# pc_max30001_brk_v1_0.net
KiCad netlist of a schematic drawn in EAGLE
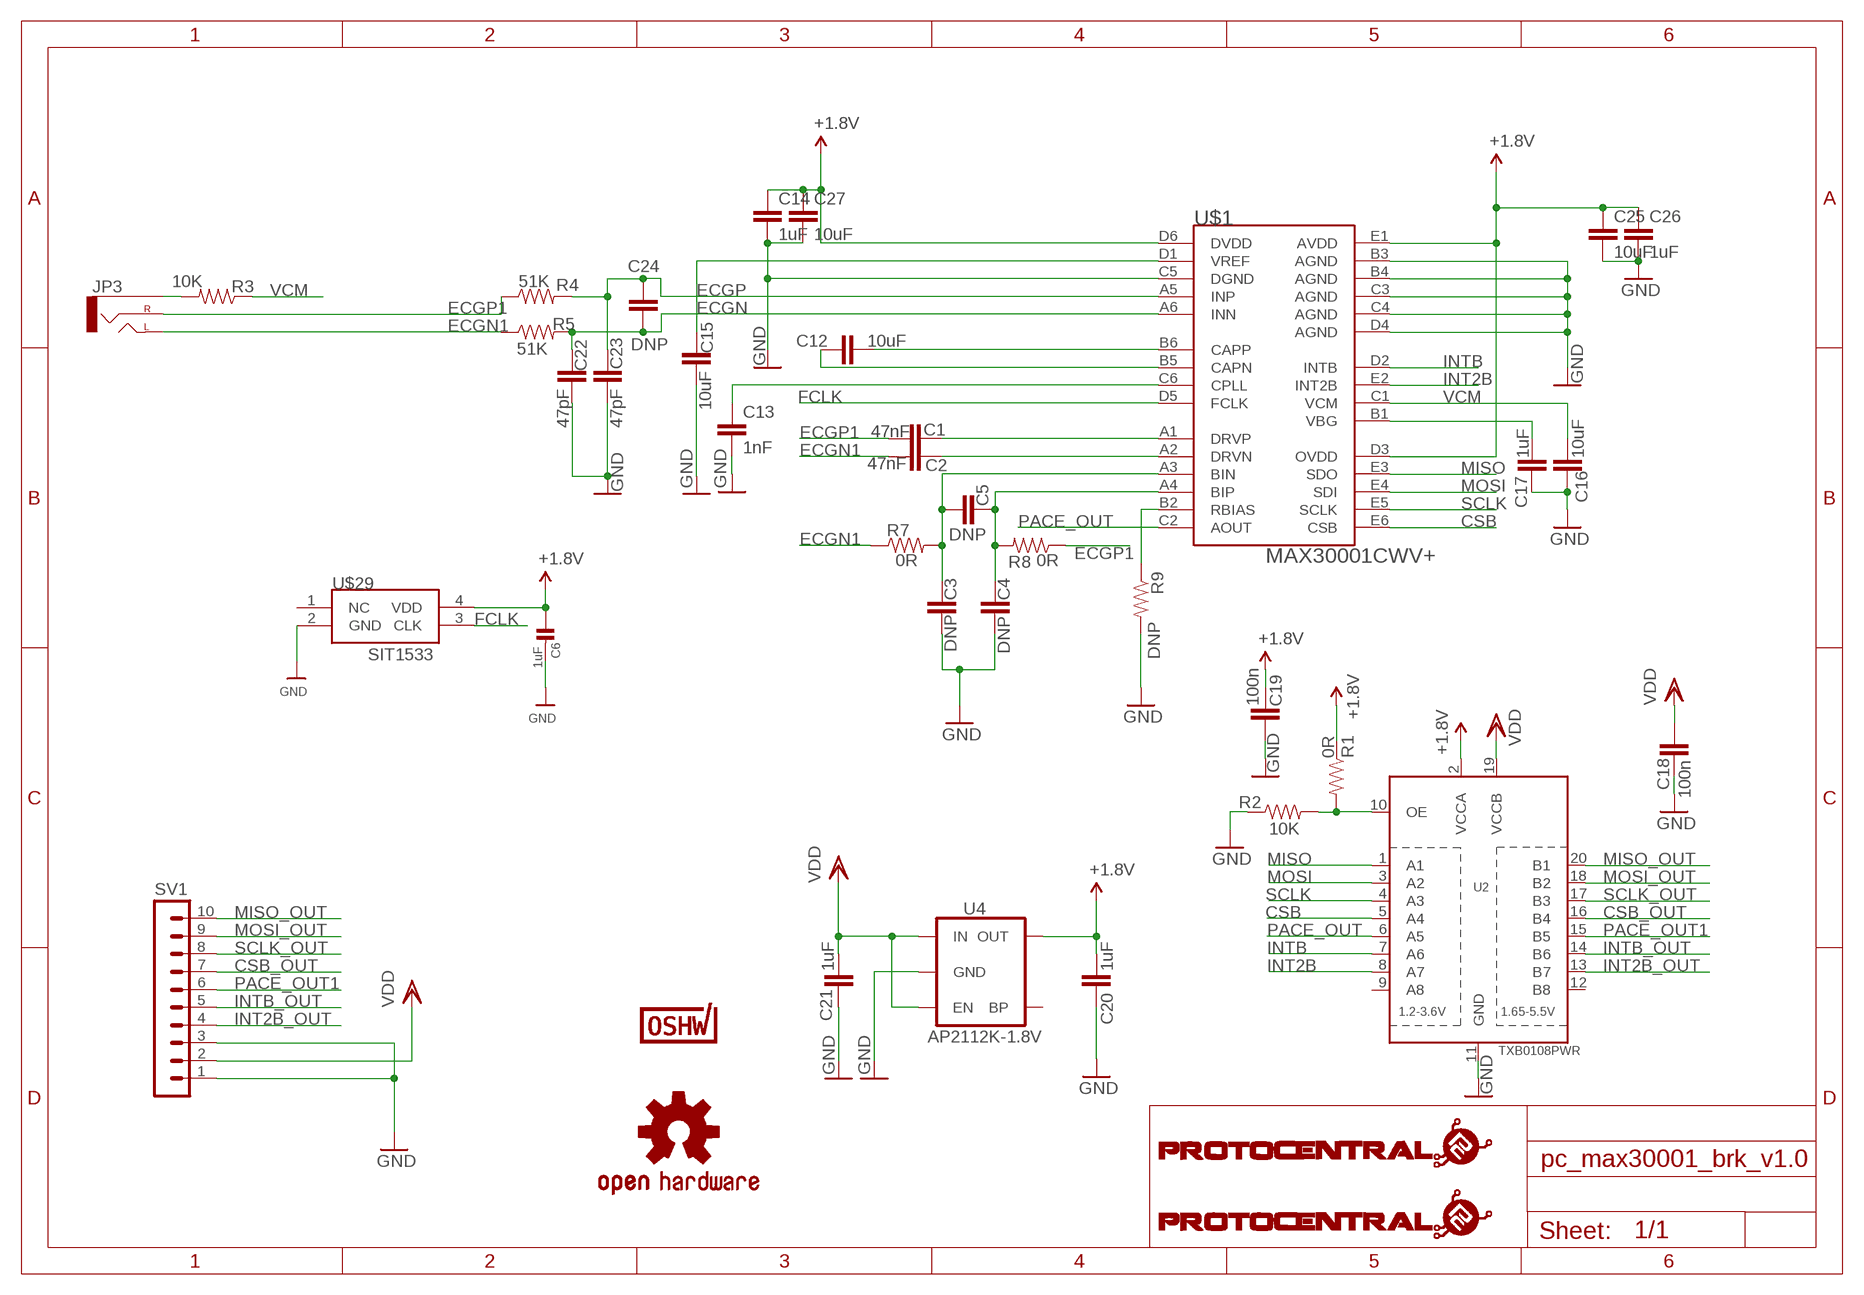
[diagram p0: schematic, sheet 1]

(export (version "E")
  (design (tool "Eeschema 10.0.6"))
  (components
    (comp (ref "C1")
      (value "47nF")
      (footprint "eagle-import:C0402")
      (libsource (lib "eagle-import") (part "C-EUC0402"))
    )
    (comp (ref "C2")
      (value "47nF")
      (footprint "eagle-import:C0402")
      (libsource (lib "eagle-import") (part "C-EUC0402"))
    )
    (comp (ref "C3")
      (value "DNP")
      (footprint "eagle-import:C0402")
      (libsource (lib "eagle-import") (part "C-EUC0402"))
    )
    (comp (ref "C4")
      (value "DNP")
      (footprint "eagle-import:C0402")
      (libsource (lib "eagle-import") (part "C-EUC0402"))
    )
    (comp (ref "C5")
      (value "DNP")
      (footprint "eagle-import:C0402")
      (libsource (lib "eagle-import") (part "C-EUC0402"))
    )
    (comp (ref "C6")
      (value "1uF")
      (footprint "eagle-import:0402")
      (libsource (lib "eagle-import") (part "CAP_CERAMIC0402"))
    )
    (comp (ref "C12")
      (value "10uF")
      (footprint "eagle-import:C0805")
      (libsource (lib "eagle-import") (part "C-EUC0805"))
    )
    (comp (ref "C13")
      (value "1nF")
      (footprint "eagle-import:C0402")
      (libsource (lib "eagle-import") (part "C-EUC0402"))
    )
    (comp (ref "C14")
      (value "1uF")
      (footprint "eagle-import:C0402")
      (libsource (lib "eagle-import") (part "C-EUC0402"))
    )
    (comp (ref "C15")
      (value "10uF")
      (footprint "eagle-import:C0805")
      (libsource (lib "eagle-import") (part "C-EUC0805"))
    )
    (comp (ref "C16")
      (value "10uF")
      (footprint "eagle-import:C0805")
      (libsource (lib "eagle-import") (part "C-EUC0805"))
    )
    (comp (ref "C17")
      (value "1uF")
      (footprint "eagle-import:C0402")
      (libsource (lib "eagle-import") (part "C-EUC0402"))
    )
    (comp (ref "C18")
      (value "100n")
      (footprint "eagle-import:C0402")
      (libsource (lib "eagle-import") (part "C-EUC0402"))
    )
    (comp (ref "C19")
      (value "100n")
      (footprint "eagle-import:C0402")
      (libsource (lib "eagle-import") (part "C-EUC0402"))
    )
    (comp (ref "C20")
      (value "1uF")
      (footprint "eagle-import:C0805")
      (libsource (lib "eagle-import") (part "C-EUC0805"))
    )
    (comp (ref "C21")
      (value "1uF")
      (footprint "eagle-import:C0805")
      (libsource (lib "eagle-import") (part "C-EUC0805"))
    )
    (comp (ref "C22")
      (value "47pF")
      (footprint "eagle-import:C0402")
      (libsource (lib "eagle-import") (part "C-EUC0402"))
    )
    (comp (ref "C23")
      (value "47pF")
      (footprint "eagle-import:C0402")
      (libsource (lib "eagle-import") (part "C-EUC0402"))
    )
    (comp (ref "C24")
      (value "DNP")
      (footprint "eagle-import:C0402")
      (libsource (lib "eagle-import") (part "C-EUC0402"))
    )
    (comp (ref "C25")
      (value "10uF")
      (footprint "eagle-import:C0805")
      (libsource (lib "eagle-import") (part "C-EUC0805"))
    )
    (comp (ref "C26")
      (value "1uF")
      (footprint "eagle-import:C0402")
      (libsource (lib "eagle-import") (part "C-EUC0402"))
    )
    (comp (ref "C27")
      (value "10uF")
      (footprint "eagle-import:C0805")
      (libsource (lib "eagle-import") (part "C-EUC0805"))
    )
    (comp (ref "JP3")
      (value "AUDIO-JACKSMD2")
      (footprint "eagle-import:AUDIO-JACK-3.5MM-SMD")
      (libsource (lib "eagle-import") (part "AUDIO-JACKSMD2"))
    )
    (comp (ref "R1")
      (value "0R")
      (footprint "eagle-import:0805")
      (libsource (lib "eagle-import") (part "RESISTOR0805-RES"))
    )
    (comp (ref "R2")
      (value "10K")
      (footprint "eagle-import:0805")
      (libsource (lib "eagle-import") (part "RESISTOR0805-RES"))
    )
    (comp (ref "R3")
      (value "10K")
      (footprint "eagle-import:0805")
      (libsource (lib "eagle-import") (part "RESISTOR0805-RES"))
    )
    (comp (ref "R4")
      (value "51K")
      (footprint "eagle-import:0805")
      (libsource (lib "eagle-import") (part "RESISTOR0805-RES"))
    )
    (comp (ref "R5")
      (value "51K")
      (footprint "eagle-import:0805")
      (libsource (lib "eagle-import") (part "RESISTOR0805-RES"))
    )
    (comp (ref "R7")
      (value "0R")
      (footprint "eagle-import:0402-RES")
      (libsource (lib "eagle-import") (part "RESISTOR0402-RES"))
    )
    (comp (ref "R8")
      (value "0R")
      (footprint "eagle-import:0402-RES")
      (libsource (lib "eagle-import") (part "RESISTOR0402-RES"))
    )
    (comp (ref "R9")
      (value "DNP")
      (footprint "eagle-import:0402-RES")
      (libsource (lib "eagle-import") (part "RESISTOR0402-RES"))
    )
    (comp (ref "SV1")
      (value "MA10-1")
      (footprint "eagle-import:MA10-1")
      (libsource (lib "eagle-import") (part "MA10-1"))
    )
    (comp (ref "U$1")
      (value "MAX30001CWV+")
      (footprint "eagle-import:30WLP")
      (libsource (lib "eagle-import") (part "MAX30001CWV+"))
    )
    (comp (ref "U$3")
      (value "PROTY-LOGO")
      (footprint "eagle-import:LOGO-PROTY")
      (libsource (lib "eagle-import") (part "PROTY-LOGO"))
    )
    (comp (ref "U$4")
      (value "PROTY_LOGO_WITH_TEXT")
      (footprint "eagle-import:PROTY_WITH_TEXT")
      (libsource (lib "eagle-import") (part "PROTY_LOGO_WITH_TEXT"))
    )
    (comp (ref "U$6")
      (value "OSHW-LOGOS")
      (footprint "eagle-import:OSHW-LOGO-S")
      (libsource (lib "eagle-import") (part "OSHW-LOGOS"))
    )
    (comp (ref "U$7")
      (value "CERT-SMALL")
      (footprint "eagle-import:CERT-SMALL-SILK")
      (libsource (lib "eagle-import") (part "CERT-SMALL"))
    )
    (comp (ref "U$29")
      (value "SIT1533")
      (footprint "eagle-import:SIT1533")
      (libsource (lib "eagle-import") (part "SIT1533"))
    )
    (comp (ref "U2")
      (value "TXB0108PWR")
      (footprint "eagle-import:TSSOP20")
      (libsource (lib "eagle-import") (part "TXB0108PWR"))
    )
    (comp (ref "U4")
      (value "AP2112K-1.8V")
      (footprint "eagle-import:SOT23-5")
      (libsource (lib "eagle-import") (part "V_REG_LDOSMD"))
    )
  )
  (nets
    (net (code "1") (name "+1.8V") (class "Default")
      (node (ref "C14") (pin "1") (pinfunction "1_1") (pintype "passive"))
      (node (ref "C19") (pin "2") (pinfunction "2_2") (pintype "passive"))
      (node (ref "C20") (pin "2") (pinfunction "2_2") (pintype "passive"))
      (node (ref "C25") (pin "1") (pinfunction "1_1") (pintype "passive"))
      (node (ref "C26") (pin "1") (pinfunction "1_1") (pintype "passive"))
      (node (ref "C27") (pin "1") (pinfunction "1_1") (pintype "passive"))
      (node (ref "C6") (pin "1") (pinfunction "P$1_1") (pintype "passive"))
      (node (ref "R1") (pin "1") (pinfunction "1_1") (pintype "passive"))
      (node (ref "U$1") (pin "D3") (pinfunction "OVDD_D3") (pintype "bidirectional"))
      (node (ref "U$1") (pin "D6") (pinfunction "DVDD_D6") (pintype "bidirectional"))
      (node (ref "U$1") (pin "E1") (pinfunction "AVDD_E1") (pintype "bidirectional"))
      (node (ref "U$29") (pin "4") (pinfunction "VDD_4") (pintype "bidirectional"))
      (node (ref "U2") (pin "2") (pinfunction "VCCA_2") (pintype "bidirectional"))
      (node (ref "U4") (pin "5") (pinfunction "OUT_5") (pintype "passive"))
    )
    (net (code "2") (name "/CSB") (class "Default")
      (node (ref "U$1") (pin "E6") (pinfunction "CSB_E6") (pintype "bidirectional"))
      (node (ref "U2") (pin "5") (pinfunction "A4_5") (pintype "bidirectional"))
    )
    (net (code "3") (name "/CSB_OUT") (class "Default")
      (node (ref "SV1") (pin "7") (pinfunction "7_7") (pintype "passive"))
      (node (ref "U2") (pin "16") (pinfunction "B4_16") (pintype "bidirectional"))
    )
    (net (code "4") (name "/ECGN") (class "Default")
      (node (ref "C22") (pin "1") (pinfunction "1_1") (pintype "passive"))
      (node (ref "C24") (pin "2") (pinfunction "2_2") (pintype "passive"))
      (node (ref "R5") (pin "2") (pinfunction "2_2") (pintype "passive"))
      (node (ref "U$1") (pin "A6") (pinfunction "INN_A6") (pintype "bidirectional"))
    )
    (net (code "5") (name "/ECGN1") (class "Default")
      (node (ref "C2") (pin "1") (pinfunction "1_1") (pintype "passive"))
      (node (ref "JP3") (pin "TIP") (pinfunction "LEFT_TIP") (pintype "bidirectional"))
      (node (ref "R5") (pin "1") (pinfunction "1_1") (pintype "passive"))
      (node (ref "R7") (pin "1") (pinfunction "1_1") (pintype "passive"))
    )
    (net (code "6") (name "/ECGP") (class "Default")
      (node (ref "C23") (pin "1") (pinfunction "1_1") (pintype "passive"))
      (node (ref "C24") (pin "1") (pinfunction "1_1") (pintype "passive"))
      (node (ref "R4") (pin "2") (pinfunction "2_2") (pintype "passive"))
      (node (ref "U$1") (pin "A5") (pinfunction "INP_A5") (pintype "bidirectional"))
    )
    (net (code "7") (name "/ECGP1") (class "Default")
      (node (ref "C1") (pin "1") (pinfunction "1_1") (pintype "passive"))
      (node (ref "JP3") (pin "RING") (pinfunction "RIGHT_RING") (pintype "bidirectional"))
      (node (ref "R4") (pin "1") (pinfunction "1_1") (pintype "passive"))
      (node (ref "R8") (pin "1") (pinfunction "1_1") (pintype "passive"))
    )
    (net (code "8") (name "/FCLK") (class "Default")
      (node (ref "U$1") (pin "D5") (pinfunction "FCLK_D5") (pintype "bidirectional"))
      (node (ref "U$29") (pin "3") (pinfunction "CLK_3") (pintype "bidirectional"))
    )
    (net (code "9") (name "/INT2B") (class "Default")
      (node (ref "U$1") (pin "E2") (pinfunction "INT2B_E2") (pintype "bidirectional"))
      (node (ref "U2") (pin "8") (pinfunction "A7_8") (pintype "bidirectional"))
    )
    (net (code "10") (name "/INT2B_OUT") (class "Default")
      (node (ref "SV1") (pin "4") (pinfunction "4_4") (pintype "passive"))
      (node (ref "U2") (pin "13") (pinfunction "B7_13") (pintype "bidirectional"))
    )
    (net (code "11") (name "/INTB") (class "Default")
      (node (ref "U$1") (pin "D2") (pinfunction "INTB_D2") (pintype "bidirectional"))
      (node (ref "U2") (pin "7") (pinfunction "A6_7") (pintype "bidirectional"))
    )
    (net (code "12") (name "/INTB_OUT") (class "Default")
      (node (ref "SV1") (pin "5") (pinfunction "5_5") (pintype "passive"))
      (node (ref "U2") (pin "14") (pinfunction "B6_14") (pintype "bidirectional"))
    )
    (net (code "13") (name "/MISO") (class "Default")
      (node (ref "U$1") (pin "E3") (pinfunction "SDO_E3") (pintype "bidirectional"))
      (node (ref "U2") (pin "1") (pinfunction "A1_1") (pintype "bidirectional"))
    )
    (net (code "14") (name "/MISO_OUT") (class "Default")
      (node (ref "SV1") (pin "10") (pinfunction "10_10") (pintype "passive"))
      (node (ref "U2") (pin "20") (pinfunction "B1_20") (pintype "bidirectional"))
    )
    (net (code "15") (name "/MOSI") (class "Default")
      (node (ref "U$1") (pin "E4") (pinfunction "SDI_E4") (pintype "bidirectional"))
      (node (ref "U2") (pin "3") (pinfunction "A2_3") (pintype "bidirectional"))
    )
    (net (code "16") (name "/MOSI_OUT") (class "Default")
      (node (ref "SV1") (pin "9") (pinfunction "9_9") (pintype "passive"))
      (node (ref "U2") (pin "18") (pinfunction "B2_18") (pintype "bidirectional"))
    )
    (net (code "17") (name "/PACE_OUT") (class "Default")
      (node (ref "U$1") (pin "C2") (pinfunction "AOUT_C2") (pintype "bidirectional"))
      (node (ref "U2") (pin "6") (pinfunction "A5_6") (pintype "bidirectional"))
    )
    (net (code "18") (name "/PACE_OUT1") (class "Default")
      (node (ref "SV1") (pin "6") (pinfunction "6_6") (pintype "passive"))
      (node (ref "U2") (pin "15") (pinfunction "B5_15") (pintype "bidirectional"))
    )
    (net (code "19") (name "/SCLK") (class "Default")
      (node (ref "U$1") (pin "E5") (pinfunction "SCLK_E5") (pintype "bidirectional"))
      (node (ref "U2") (pin "4") (pinfunction "A3_4") (pintype "bidirectional"))
    )
    (net (code "20") (name "/SCLK_OUT") (class "Default")
      (node (ref "SV1") (pin "8") (pinfunction "8_8") (pintype "passive"))
      (node (ref "U2") (pin "17") (pinfunction "B3_17") (pintype "bidirectional"))
    )
    (net (code "21") (name "/VCM") (class "Default")
      (node (ref "C16") (pin "1") (pinfunction "1_1") (pintype "passive"))
      (node (ref "R3") (pin "1") (pinfunction "1_1") (pintype "passive"))
      (node (ref "U$1") (pin "C1") (pinfunction "VCM_C1") (pintype "bidirectional"))
    )
    (net (code "22") (name "GND") (class "Default")
      (node (ref "C13") (pin "2") (pinfunction "2_2") (pintype "passive"))
      (node (ref "C14") (pin "2") (pinfunction "2_2") (pintype "passive"))
      (node (ref "C15") (pin "2") (pinfunction "2_2") (pintype "passive"))
      (node (ref "C16") (pin "2") (pinfunction "2_2") (pintype "passive"))
      (node (ref "C17") (pin "2") (pinfunction "2_2") (pintype "passive"))
      (node (ref "C18") (pin "1") (pinfunction "1_1") (pintype "passive"))
      (node (ref "C19") (pin "1") (pinfunction "1_1") (pintype "passive"))
      (node (ref "C20") (pin "1") (pinfunction "1_1") (pintype "passive"))
      (node (ref "C21") (pin "1") (pinfunction "1_1") (pintype "passive"))
      (node (ref "C22") (pin "2") (pinfunction "2_2") (pintype "passive"))
      (node (ref "C23") (pin "2") (pinfunction "2_2") (pintype "passive"))
      (node (ref "C25") (pin "2") (pinfunction "2_2") (pintype "passive"))
      (node (ref "C26") (pin "2") (pinfunction "2_2") (pintype "passive"))
      (node (ref "C27") (pin "2") (pinfunction "2_2") (pintype "passive"))
      (node (ref "C3") (pin "2") (pinfunction "2_2") (pintype "passive"))
      (node (ref "C4") (pin "2") (pinfunction "2_2") (pintype "passive"))
      (node (ref "C6") (pin "2") (pinfunction "P$2_2") (pintype "passive"))
      (node (ref "R2") (pin "1") (pinfunction "1_1") (pintype "passive"))
      (node (ref "R9") (pin "2") (pinfunction "2_2") (pintype "passive"))
      (node (ref "SV1") (pin "1") (pinfunction "1_1") (pintype "passive"))
      (node (ref "SV1") (pin "3") (pinfunction "3_3") (pintype "passive"))
      (node (ref "U$1") (pin "B3") (pinfunction "AGND_B3") (pintype "bidirectional"))
      (node (ref "U$1") (pin "B4") (pinfunction "AGND_B4") (pintype "bidirectional"))
      (node (ref "U$1") (pin "C3") (pinfunction "AGND_C3") (pintype "bidirectional"))
      (node (ref "U$1") (pin "C4") (pinfunction "AGND_C4") (pintype "bidirectional"))
      (node (ref "U$1") (pin "C5") (pinfunction "DGND_C5") (pintype "bidirectional"))
      (node (ref "U$1") (pin "D4") (pinfunction "AGND_D4") (pintype "bidirectional"))
      (node (ref "U$29") (pin "2") (pinfunction "GND_2") (pintype "bidirectional"))
      (node (ref "U2") (pin "11") (pinfunction "GND_11") (pintype "bidirectional"))
      (node (ref "U4") (pin "2") (pinfunction "GND_2") (pintype "input"))
    )
    (net (code "23") (name "Net-(JP3-PadSLEEVE)") (class "Default")
      (node (ref "JP3") (pin "SLEEVE") (pinfunction "SLEEVE_SLEEVE") (pintype "bidirectional"))
      (node (ref "R3") (pin "2") (pinfunction "2_2") (pintype "passive"))
    )
    (net (code "24") (name "Net-(U$1-BIN)") (class "Default")
      (node (ref "C3") (pin "1") (pinfunction "1_1") (pintype "passive"))
      (node (ref "C5") (pin "1") (pinfunction "1_1") (pintype "passive"))
      (node (ref "R7") (pin "2") (pinfunction "2_2") (pintype "passive"))
      (node (ref "U$1") (pin "A3") (pinfunction "BIN_A3") (pintype "bidirectional"))
    )
    (net (code "25") (name "Net-(U$1-BIP)") (class "Default")
      (node (ref "C4") (pin "1") (pinfunction "1_1") (pintype "passive"))
      (node (ref "C5") (pin "2") (pinfunction "2_2") (pintype "passive"))
      (node (ref "R8") (pin "2") (pinfunction "2_2") (pintype "passive"))
      (node (ref "U$1") (pin "A4") (pinfunction "BIP_A4") (pintype "bidirectional"))
    )
    (net (code "26") (name "Net-(U$1-CAPN)") (class "Default")
      (node (ref "C12") (pin "2") (pinfunction "2_2") (pintype "passive"))
      (node (ref "U$1") (pin "B5") (pinfunction "CAPN_B5") (pintype "bidirectional"))
    )
    (net (code "27") (name "Net-(U$1-CAPP)") (class "Default")
      (node (ref "C12") (pin "1") (pinfunction "1_1") (pintype "passive"))
      (node (ref "U$1") (pin "B6") (pinfunction "CAPP_B6") (pintype "bidirectional"))
    )
    (net (code "28") (name "Net-(U$1-CPLL)") (class "Default")
      (node (ref "C13") (pin "1") (pinfunction "1_1") (pintype "passive"))
      (node (ref "U$1") (pin "C6") (pinfunction "CPLL_C6") (pintype "bidirectional"))
    )
    (net (code "29") (name "Net-(U$1-DRVN)") (class "Default")
      (node (ref "C2") (pin "2") (pinfunction "2_2") (pintype "passive"))
      (node (ref "U$1") (pin "A2") (pinfunction "DRVN_A2") (pintype "bidirectional"))
    )
    (net (code "30") (name "Net-(U$1-DRVP)") (class "Default")
      (node (ref "C1") (pin "2") (pinfunction "2_2") (pintype "passive"))
      (node (ref "U$1") (pin "A1") (pinfunction "DRVP_A1") (pintype "bidirectional"))
    )
    (net (code "31") (name "Net-(U$1-RBIAS)") (class "Default")
      (node (ref "R9") (pin "1") (pinfunction "1_1") (pintype "passive"))
      (node (ref "U$1") (pin "B2") (pinfunction "RBIAS_B2") (pintype "bidirectional"))
    )
    (net (code "32") (name "Net-(U$1-VBG)") (class "Default")
      (node (ref "C17") (pin "1") (pinfunction "1_1") (pintype "passive"))
      (node (ref "U$1") (pin "B1") (pinfunction "VBG_B1") (pintype "bidirectional"))
    )
    (net (code "33") (name "Net-(U$1-VREF)") (class "Default")
      (node (ref "C15") (pin "1") (pinfunction "1_1") (pintype "passive"))
      (node (ref "U$1") (pin "D1") (pinfunction "VREF_D1") (pintype "bidirectional"))
    )
    (net (code "34") (name "Net-(U2-OE)") (class "Default")
      (node (ref "R1") (pin "2") (pinfunction "2_2") (pintype "passive"))
      (node (ref "R2") (pin "2") (pinfunction "2_2") (pintype "passive"))
      (node (ref "U2") (pin "10") (pinfunction "OE_10") (pintype "bidirectional"))
    )
    (net (code "35") (name "VDD") (class "Default")
      (node (ref "C18") (pin "2") (pinfunction "2_2") (pintype "passive"))
      (node (ref "C21") (pin "2") (pinfunction "2_2") (pintype "passive"))
      (node (ref "SV1") (pin "2") (pinfunction "2_2") (pintype "passive"))
      (node (ref "U2") (pin "19") (pinfunction "VCCB_19") (pintype "bidirectional"))
      (node (ref "U4") (pin "1") (pinfunction "IN_1") (pintype "input"))
      (node (ref "U4") (pin "3") (pinfunction "EN_3") (pintype "input"))
    )
    (net (code "36") (name "unconnected-(U$29-NC-Pad1)") (class "Default")
      (node (ref "U$29") (pin "1") (pinfunction "NC_1") (pintype "bidirectional"))
    )
    (net (code "37") (name "unconnected-(U2-A8-Pad9)") (class "Default")
      (node (ref "U2") (pin "9") (pinfunction "A8_9") (pintype "bidirectional"))
    )
    (net (code "38") (name "unconnected-(U2-B8-Pad12)") (class "Default")
      (node (ref "U2") (pin "12") (pinfunction "B8_12") (pintype "bidirectional"))
    )
    (net (code "39") (name "unconnected-(U4-BP-Pad4)") (class "Default")
      (node (ref "U4") (pin "4") (pinfunction "BP_4") (pintype "input"))
    )
  )
)
